# Sensor_LF_V_2B.net
KiCad netlist of a schematic drawn in EAGLE
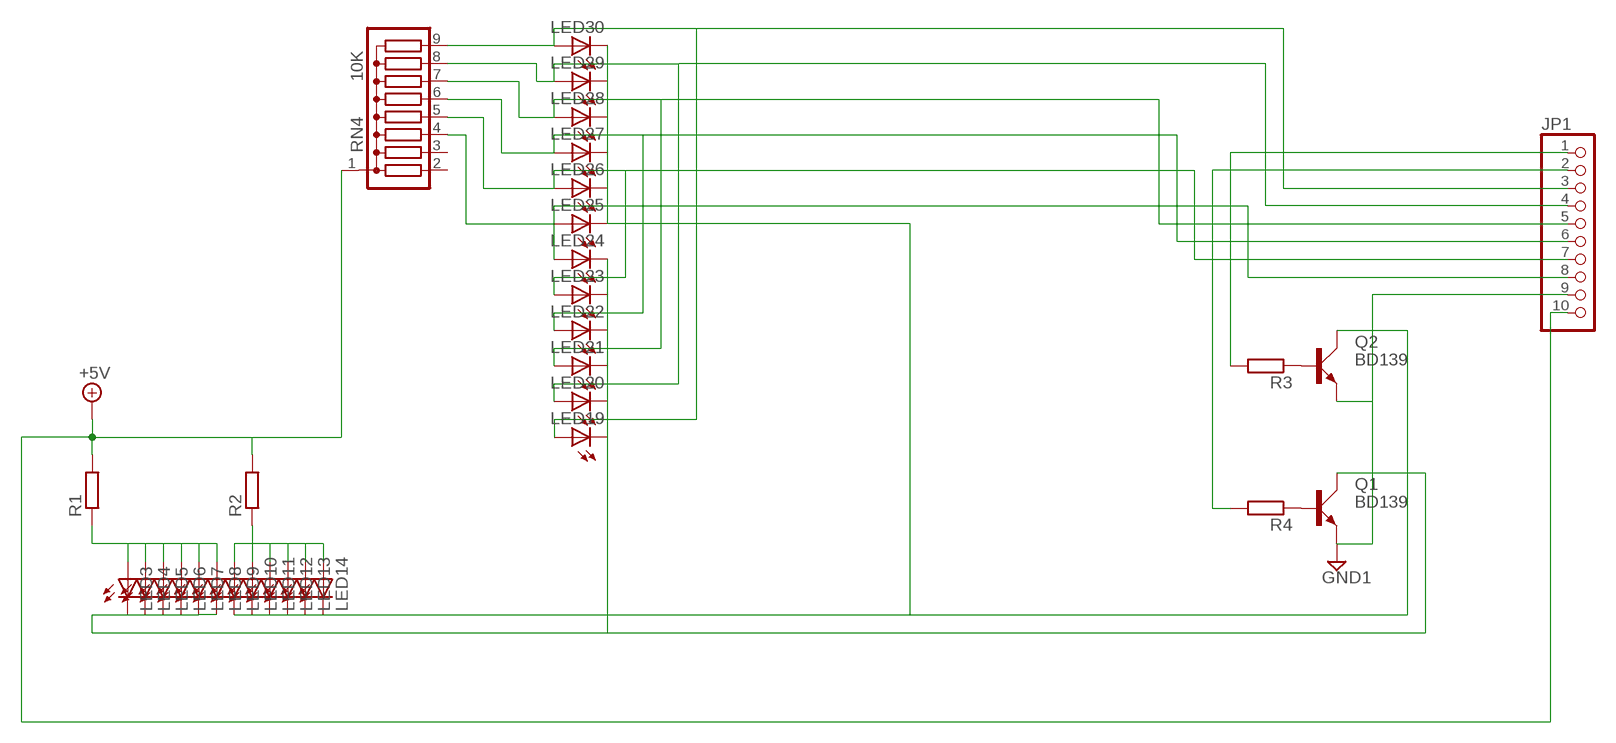
[diagram p0: schematic, sheet 1]

(export (version "E")
  (design (tool "Eeschema 10.0.6"))
  (components
    (comp (ref "JP1")
      (value "PINHD-1X10")
      (footprint "eagle-import:1X10")
      (libsource (lib "eagle-import") (part "PINHD-1X10"))
    )
    (comp (ref "LED3")
      (value "LED3MM")
      (footprint "eagle-import:LED3MM")
      (libsource (lib "eagle-import") (part "LED3MM"))
    )
    (comp (ref "LED4")
      (value "LED3MM")
      (footprint "eagle-import:LED3MM")
      (libsource (lib "eagle-import") (part "LED3MM"))
    )
    (comp (ref "LED5")
      (value "LED3MM")
      (footprint "eagle-import:LED3MM")
      (libsource (lib "eagle-import") (part "LED3MM"))
    )
    (comp (ref "LED6")
      (value "LED3MM")
      (footprint "eagle-import:LED3MM")
      (libsource (lib "eagle-import") (part "LED3MM"))
    )
    (comp (ref "LED7")
      (value "LED3MM")
      (footprint "eagle-import:LED3MM")
      (libsource (lib "eagle-import") (part "LED3MM"))
    )
    (comp (ref "LED8")
      (value "LED3MM")
      (footprint "eagle-import:LED3MM")
      (libsource (lib "eagle-import") (part "LED3MM"))
    )
    (comp (ref "LED9")
      (value "LED3MM")
      (footprint "eagle-import:LED3MM")
      (libsource (lib "eagle-import") (part "LED3MM"))
    )
    (comp (ref "LED10")
      (value "LED3MM")
      (footprint "eagle-import:LED3MM")
      (libsource (lib "eagle-import") (part "LED3MM"))
    )
    (comp (ref "LED11")
      (value "LED3MM")
      (footprint "eagle-import:LED3MM")
      (libsource (lib "eagle-import") (part "LED3MM"))
    )
    (comp (ref "LED12")
      (value "LED3MM")
      (footprint "eagle-import:LED3MM")
      (libsource (lib "eagle-import") (part "LED3MM"))
    )
    (comp (ref "LED13")
      (value "LED3MM")
      (footprint "eagle-import:LED3MM")
      (libsource (lib "eagle-import") (part "LED3MM"))
    )
    (comp (ref "LED14")
      (value "LED3MM")
      (footprint "eagle-import:LED3MM")
      (libsource (lib "eagle-import") (part "LED3MM"))
    )
    (comp (ref "LED19")
      (value "LED3MM")
      (footprint "eagle-import:LED3MM")
      (libsource (lib "eagle-import") (part "LED3MM"))
    )
    (comp (ref "LED20")
      (value "LED3MM")
      (footprint "eagle-import:LED3MM")
      (libsource (lib "eagle-import") (part "LED3MM"))
    )
    (comp (ref "LED21")
      (value "LED3MM")
      (footprint "eagle-import:LED3MM")
      (libsource (lib "eagle-import") (part "LED3MM"))
    )
    (comp (ref "LED22")
      (value "LED3MM")
      (footprint "eagle-import:LED3MM")
      (libsource (lib "eagle-import") (part "LED3MM"))
    )
    (comp (ref "LED23")
      (value "LED3MM")
      (footprint "eagle-import:LED3MM")
      (libsource (lib "eagle-import") (part "LED3MM"))
    )
    (comp (ref "LED24")
      (value "LED3MM")
      (footprint "eagle-import:LED3MM")
      (libsource (lib "eagle-import") (part "LED3MM"))
    )
    (comp (ref "LED25")
      (value "LED3MM")
      (footprint "eagle-import:LED3MM")
      (libsource (lib "eagle-import") (part "LED3MM"))
    )
    (comp (ref "LED26")
      (value "LED3MM")
      (footprint "eagle-import:LED3MM")
      (libsource (lib "eagle-import") (part "LED3MM"))
    )
    (comp (ref "LED27")
      (value "LED3MM")
      (footprint "eagle-import:LED3MM")
      (libsource (lib "eagle-import") (part "LED3MM"))
    )
    (comp (ref "LED28")
      (value "LED3MM")
      (footprint "eagle-import:LED3MM")
      (libsource (lib "eagle-import") (part "LED3MM"))
    )
    (comp (ref "LED29")
      (value "LED3MM")
      (footprint "eagle-import:LED3MM")
      (libsource (lib "eagle-import") (part "LED3MM"))
    )
    (comp (ref "LED30")
      (value "LED3MM")
      (footprint "eagle-import:LED3MM")
      (libsource (lib "eagle-import") (part "LED3MM"))
    )
    (comp (ref "Q1")
      (value "BD139")
      (footprint "eagle-import:TO126AV")
      (libsource (lib "eagle-import") (part "BD139"))
    )
    (comp (ref "Q2")
      (value "BD139")
      (footprint "eagle-import:TO126AV")
      (libsource (lib "eagle-import") (part "BD139"))
    )
    (comp (ref "R1")
      (value "R-EU_0207/10")
      (footprint "eagle-import:0207_10")
      (libsource (lib "eagle-import") (part "R-EU_0207/10"))
    )
    (comp (ref "R2")
      (value "R-EU_0207/10")
      (footprint "eagle-import:0207_10")
      (libsource (lib "eagle-import") (part "R-EU_0207/10"))
    )
    (comp (ref "R3")
      (value "R-EU_0207/10")
      (footprint "eagle-import:0207_10")
      (libsource (lib "eagle-import") (part "R-EU_0207/10"))
    )
    (comp (ref "R4")
      (value "R-EU_0207/10")
      (footprint "eagle-import:0207_10")
      (libsource (lib "eagle-import") (part "R-EU_0207/10"))
    )
    (comp (ref "RN4")
      (value "10K")
      (footprint "eagle-import:SIL9")
      (libsource (lib "eagle-import") (part "G08R"))
    )
  )
  (nets
    (net (code "1") (name "+5V") (class "Default")
      (node (ref "JP1") (pin "10") (pinfunction "10_10") (pintype "passive"))
      (node (ref "R1") (pin "2") (pinfunction "2_2") (pintype "passive"))
      (node (ref "R2") (pin "2") (pinfunction "2_2") (pintype "passive"))
      (node (ref "RN4") (pin "1") (pinfunction "1_1") (pintype "passive"))
    )
    (net (code "2") (name "GND1") (class "Default")
      (node (ref "JP1") (pin "9") (pinfunction "9_9") (pintype "passive"))
      (node (ref "Q1") (pin "E") (pinfunction "E_E") (pintype "passive"))
      (node (ref "Q2") (pin "E") (pinfunction "E_E") (pintype "passive"))
    )
    (net (code "3") (name "Net-(JP1-Pad1)") (class "Default")
      (node (ref "JP1") (pin "1") (pinfunction "1_1") (pintype "passive"))
      (node (ref "R3") (pin "2") (pinfunction "2_2") (pintype "passive"))
    )
    (net (code "4") (name "Net-(JP1-Pad2)") (class "Default")
      (node (ref "JP1") (pin "2") (pinfunction "2_2") (pintype "passive"))
      (node (ref "R4") (pin "2") (pinfunction "2_2") (pintype "passive"))
    )
    (net (code "5") (name "Net-(JP1-Pad3)") (class "Default")
      (node (ref "JP1") (pin "3") (pinfunction "3_3") (pintype "passive"))
      (node (ref "LED19") (pin "A") (pinfunction "A_A") (pintype "passive"))
      (node (ref "LED30") (pin "A") (pinfunction "A_A") (pintype "passive"))
      (node (ref "RN4") (pin "9") (pinfunction "9_9") (pintype "passive"))
    )
    (net (code "6") (name "Net-(JP1-Pad4)") (class "Default")
      (node (ref "JP1") (pin "4") (pinfunction "4_4") (pintype "passive"))
      (node (ref "LED20") (pin "A") (pinfunction "A_A") (pintype "passive"))
      (node (ref "LED29") (pin "A") (pinfunction "A_A") (pintype "passive"))
      (node (ref "RN4") (pin "8") (pinfunction "8_8") (pintype "passive"))
    )
    (net (code "7") (name "Net-(JP1-Pad5)") (class "Default")
      (node (ref "JP1") (pin "5") (pinfunction "5_5") (pintype "passive"))
      (node (ref "LED21") (pin "A") (pinfunction "A_A") (pintype "passive"))
      (node (ref "LED28") (pin "A") (pinfunction "A_A") (pintype "passive"))
      (node (ref "RN4") (pin "7") (pinfunction "7_7") (pintype "passive"))
    )
    (net (code "8") (name "Net-(JP1-Pad6)") (class "Default")
      (node (ref "JP1") (pin "6") (pinfunction "6_6") (pintype "passive"))
      (node (ref "LED22") (pin "A") (pinfunction "A_A") (pintype "passive"))
      (node (ref "LED27") (pin "A") (pinfunction "A_A") (pintype "passive"))
      (node (ref "RN4") (pin "6") (pinfunction "6_6") (pintype "passive"))
    )
    (net (code "9") (name "Net-(JP1-Pad7)") (class "Default")
      (node (ref "JP1") (pin "7") (pinfunction "7_7") (pintype "passive"))
      (node (ref "LED23") (pin "A") (pinfunction "A_A") (pintype "passive"))
      (node (ref "LED26") (pin "A") (pinfunction "A_A") (pintype "passive"))
      (node (ref "RN4") (pin "5") (pinfunction "5_5") (pintype "passive"))
    )
    (net (code "10") (name "Net-(JP1-Pad8)") (class "Default")
      (node (ref "JP1") (pin "8") (pinfunction "8_8") (pintype "passive"))
      (node (ref "LED24") (pin "A") (pinfunction "A_A") (pintype "passive"))
      (node (ref "LED25") (pin "A") (pinfunction "A_A") (pintype "passive"))
      (node (ref "RN4") (pin "4") (pinfunction "4_4") (pintype "passive"))
    )
    (net (code "11") (name "Net-(LED3-PadA)") (class "Default")
      (node (ref "LED3") (pin "A") (pinfunction "A_A") (pintype "passive"))
      (node (ref "LED4") (pin "A") (pinfunction "A_A") (pintype "passive"))
      (node (ref "LED5") (pin "A") (pinfunction "A_A") (pintype "passive"))
      (node (ref "LED6") (pin "A") (pinfunction "A_A") (pintype "passive"))
      (node (ref "LED7") (pin "A") (pinfunction "A_A") (pintype "passive"))
      (node (ref "LED8") (pin "A") (pinfunction "A_A") (pintype "passive"))
      (node (ref "R1") (pin "1") (pinfunction "1_1") (pintype "passive"))
    )
    (net (code "12") (name "Net-(LED10-C)") (class "Default")
      (node (ref "LED10") (pin "K") (pinfunction "C_K") (pintype "passive"))
      (node (ref "LED11") (pin "K") (pinfunction "C_K") (pintype "passive"))
      (node (ref "LED12") (pin "K") (pinfunction "C_K") (pintype "passive"))
      (node (ref "LED13") (pin "K") (pinfunction "C_K") (pintype "passive"))
      (node (ref "LED14") (pin "K") (pinfunction "C_K") (pintype "passive"))
      (node (ref "LED25") (pin "K") (pinfunction "C_K") (pintype "passive"))
      (node (ref "LED26") (pin "K") (pinfunction "C_K") (pintype "passive"))
      (node (ref "LED27") (pin "K") (pinfunction "C_K") (pintype "passive"))
      (node (ref "LED28") (pin "K") (pinfunction "C_K") (pintype "passive"))
      (node (ref "LED29") (pin "K") (pinfunction "C_K") (pintype "passive"))
      (node (ref "LED30") (pin "K") (pinfunction "C_K") (pintype "passive"))
      (node (ref "LED9") (pin "K") (pinfunction "C_K") (pintype "passive"))
      (node (ref "Q2") (pin "C") (pinfunction "C_C") (pintype "passive"))
    )
    (net (code "13") (name "Net-(LED10-PadA)") (class "Default")
      (node (ref "LED10") (pin "A") (pinfunction "A_A") (pintype "passive"))
      (node (ref "LED11") (pin "A") (pinfunction "A_A") (pintype "passive"))
      (node (ref "LED12") (pin "A") (pinfunction "A_A") (pintype "passive"))
      (node (ref "LED13") (pin "A") (pinfunction "A_A") (pintype "passive"))
      (node (ref "LED14") (pin "A") (pinfunction "A_A") (pintype "passive"))
      (node (ref "LED9") (pin "A") (pinfunction "A_A") (pintype "passive"))
      (node (ref "R2") (pin "1") (pinfunction "1_1") (pintype "passive"))
    )
    (net (code "14") (name "Net-(LED19-C)") (class "Default")
      (node (ref "LED19") (pin "K") (pinfunction "C_K") (pintype "passive"))
      (node (ref "LED20") (pin "K") (pinfunction "C_K") (pintype "passive"))
      (node (ref "LED21") (pin "K") (pinfunction "C_K") (pintype "passive"))
      (node (ref "LED22") (pin "K") (pinfunction "C_K") (pintype "passive"))
      (node (ref "LED23") (pin "K") (pinfunction "C_K") (pintype "passive"))
      (node (ref "LED24") (pin "K") (pinfunction "C_K") (pintype "passive"))
      (node (ref "LED3") (pin "K") (pinfunction "C_K") (pintype "passive"))
      (node (ref "LED4") (pin "K") (pinfunction "C_K") (pintype "passive"))
      (node (ref "LED5") (pin "K") (pinfunction "C_K") (pintype "passive"))
      (node (ref "LED6") (pin "K") (pinfunction "C_K") (pintype "passive"))
      (node (ref "LED7") (pin "K") (pinfunction "C_K") (pintype "passive"))
      (node (ref "LED8") (pin "K") (pinfunction "C_K") (pintype "passive"))
      (node (ref "Q1") (pin "C") (pinfunction "C_C") (pintype "passive"))
    )
    (net (code "15") (name "Net-(Q1-PadB)") (class "Default")
      (node (ref "Q1") (pin "B") (pinfunction "B_B") (pintype "passive"))
      (node (ref "R4") (pin "1") (pinfunction "1_1") (pintype "passive"))
    )
    (net (code "16") (name "Net-(Q2-PadB)") (class "Default")
      (node (ref "Q2") (pin "B") (pinfunction "B_B") (pintype "passive"))
      (node (ref "R3") (pin "1") (pinfunction "1_1") (pintype "passive"))
    )
    (net (code "17") (name "unconnected-(RN4-Pad2)") (class "Default")
      (node (ref "RN4") (pin "2") (pinfunction "2_2") (pintype "passive"))
    )
    (net (code "18") (name "unconnected-(RN4-Pad3)") (class "Default")
      (node (ref "RN4") (pin "3") (pinfunction "3_3") (pintype "passive"))
    )
  )
)
